# 2_PMIC_2.net
KiCad netlist of a schematic drawn in Altium Designer
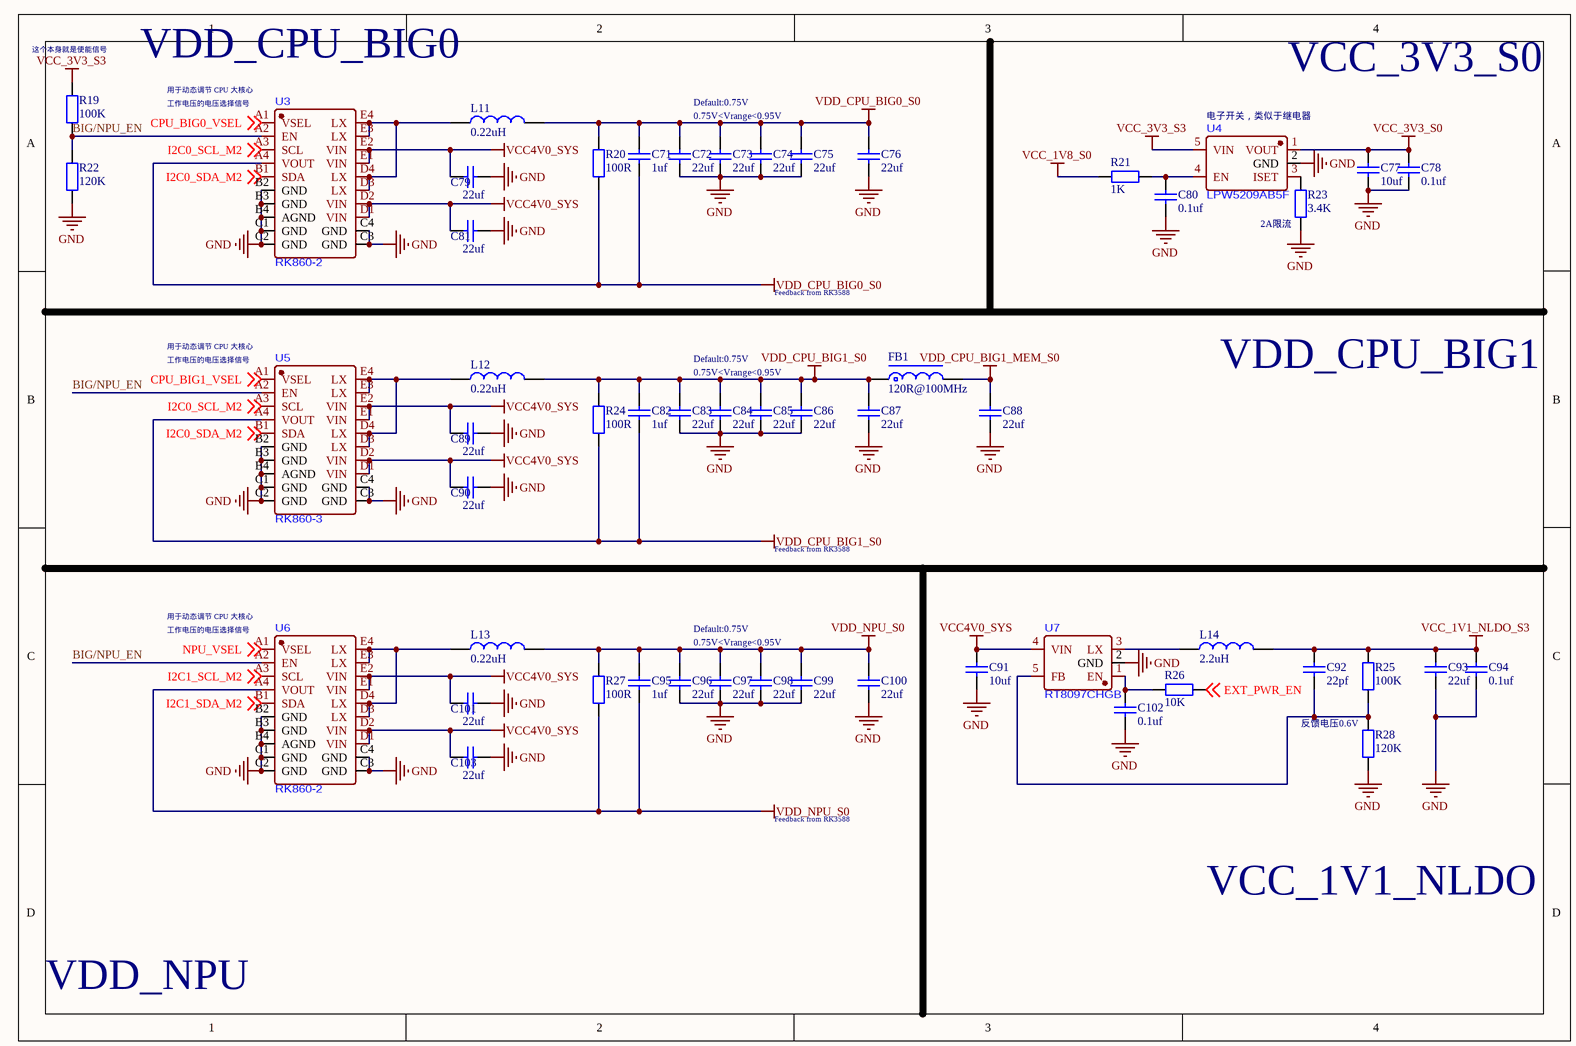
[diagram p0: 2.PMIC_2.SchDoc]

(export (version "E")
  (design (tool "Eeschema 10.0.6"))
  (components
    (comp (ref "C71")
      (value "1uf")
      (footprint "0.PCB1:C0402_L")
      (description "贴片电容/MLCC电容")
      (libsource (lib "RK3588") (part "C"))
    )
    (comp (ref "C72")
      (value "22uf")
      (footprint "0.PCB1:C0603_L")
      (description "贴片电容/MLCC电容")
      (libsource (lib "RK3588") (part "C"))
    )
    (comp (ref "C73")
      (value "22uf")
      (footprint "0.PCB1:C0603_L")
      (description "贴片电容/MLCC电容")
      (libsource (lib "RK3588") (part "C"))
    )
    (comp (ref "C74")
      (value "22uf")
      (footprint "0.PCB1:C0603_L")
      (description "贴片电容/MLCC电容")
      (libsource (lib "RK3588") (part "C"))
    )
    (comp (ref "C75")
      (value "22uf")
      (footprint "0.PCB1:C0603_L")
      (description "贴片电容/MLCC电容")
      (libsource (lib "RK3588") (part "C"))
    )
    (comp (ref "C76")
      (value "22uf")
      (footprint "0.PCB1:C0603_L")
      (description "贴片电容/MLCC电容")
      (libsource (lib "RK3588") (part "C"))
    )
    (comp (ref "C77")
      (value "10uf")
      (footprint "0.PCB1:C0402_L")
      (description "贴片电容/MLCC电容")
      (libsource (lib "RK3588") (part "C"))
    )
    (comp (ref "C78")
      (value "0.1uf")
      (footprint "0.PCB1:C0402_L")
      (description "贴片电容/MLCC电容")
      (libsource (lib "RK3588") (part "C"))
    )
    (comp (ref "C79")
      (value "22uf")
      (footprint "0.PCB1:C0603_L")
      (description "贴片电容/MLCC电容")
      (libsource (lib "RK3588") (part "C"))
    )
    (comp (ref "C80")
      (value "0.1uf")
      (footprint "0.PCB1:C0402_L")
      (description "贴片电容/MLCC电容")
      (libsource (lib "RK3588") (part "C"))
    )
    (comp (ref "C81")
      (value "22uf")
      (footprint "0.PCB1:C0603_L")
      (description "贴片电容/MLCC电容")
      (libsource (lib "RK3588") (part "C"))
    )
    (comp (ref "C82")
      (value "1uf")
      (footprint "0.PCB1:C0402_L")
      (description "贴片电容/MLCC电容")
      (libsource (lib "RK3588") (part "C"))
    )
    (comp (ref "C83")
      (value "22uf")
      (footprint "0.PCB1:C0603_L")
      (description "贴片电容/MLCC电容")
      (libsource (lib "RK3588") (part "C"))
    )
    (comp (ref "C84")
      (value "22uf")
      (footprint "0.PCB1:C0603_L")
      (description "贴片电容/MLCC电容")
      (libsource (lib "RK3588") (part "C"))
    )
    (comp (ref "C85")
      (value "22uf")
      (footprint "0.PCB1:C0603_L")
      (description "贴片电容/MLCC电容")
      (libsource (lib "RK3588") (part "C"))
    )
    (comp (ref "C86")
      (value "22uf")
      (footprint "0.PCB1:C0603_L")
      (description "贴片电容/MLCC电容")
      (libsource (lib "RK3588") (part "C"))
    )
    (comp (ref "C87")
      (value "22uf")
      (footprint "0.PCB1:C0603_L")
      (description "贴片电容/MLCC电容")
      (libsource (lib "RK3588") (part "C"))
    )
    (comp (ref "C88")
      (value "22uf")
      (footprint "0.PCB1:C0603_L")
      (description "贴片电容/MLCC电容")
      (libsource (lib "RK3588") (part "C"))
    )
    (comp (ref "C89")
      (value "22uf")
      (footprint "0.PCB1:C0603_L")
      (description "贴片电容/MLCC电容")
      (libsource (lib "RK3588") (part "C"))
    )
    (comp (ref "C90")
      (value "22uf")
      (footprint "0.PCB1:C0603_L")
      (description "贴片电容/MLCC电容")
      (libsource (lib "RK3588") (part "C"))
    )
    (comp (ref "C91")
      (value "10uf")
      (footprint "0.PCB1:C0402_L")
      (description "贴片电容/MLCC电容")
      (libsource (lib "RK3588") (part "C"))
    )
    (comp (ref "C92")
      (value "22pf")
      (footprint "0.PCB1:C0402_L")
      (description "贴片电容/MLCC电容")
      (libsource (lib "RK3588") (part "C"))
    )
    (comp (ref "C93")
      (value "22uf")
      (footprint "0.PCB1:C0603_L")
      (description "贴片电容/MLCC电容")
      (libsource (lib "RK3588") (part "C"))
    )
    (comp (ref "C94")
      (value "0.1uf")
      (footprint "0.PCB1:C0402_L")
      (description "贴片电容/MLCC电容")
      (libsource (lib "RK3588") (part "C"))
    )
    (comp (ref "C95")
      (value "1uf")
      (footprint "0.PCB1:C0402_L")
      (description "贴片电容/MLCC电容")
      (libsource (lib "RK3588") (part "C"))
    )
    (comp (ref "C96")
      (value "22uf")
      (footprint "0.PCB1:C0603_L")
      (description "贴片电容/MLCC电容")
      (libsource (lib "RK3588") (part "C"))
    )
    (comp (ref "C97")
      (value "22uf")
      (footprint "0.PCB1:C0603_L")
      (description "贴片电容/MLCC电容")
      (libsource (lib "RK3588") (part "C"))
    )
    (comp (ref "C98")
      (value "22uf")
      (footprint "0.PCB1:C0603_L")
      (description "贴片电容/MLCC电容")
      (libsource (lib "RK3588") (part "C"))
    )
    (comp (ref "C99")
      (value "22uf")
      (footprint "0.PCB1:C0603_L")
      (description "贴片电容/MLCC电容")
      (libsource (lib "RK3588") (part "C"))
    )
    (comp (ref "C100")
      (value "22uf")
      (footprint "0.PCB1:C0603_L")
      (description "贴片电容/MLCC电容")
      (libsource (lib "RK3588") (part "C"))
    )
    (comp (ref "C101")
      (value "22uf")
      (footprint "0.PCB1:C0603_L")
      (description "贴片电容/MLCC电容")
      (libsource (lib "RK3588") (part "C"))
    )
    (comp (ref "C102")
      (value "0.1uf")
      (footprint "0.PCB1:C0402_L")
      (description "贴片电容/MLCC电容")
      (libsource (lib "RK3588") (part "C"))
    )
    (comp (ref "C103")
      (value "22uf")
      (footprint "0.PCB1:C0603_L")
      (description "贴片电容/MLCC电容")
      (libsource (lib "RK3588") (part "C"))
    )
    (comp (ref "FB1")
      (value "120R@100MHz")
      (footprint "0.PCB1:FB0402")
      (description "贴片磁珠")
      (libsource (lib "RK3588") (part "FB"))
    )
    (comp (ref "L11")
      (value "0.22uH")
      (footprint "0.PCB1:L0805")
      (description "贴片小功率电感")
      (libsource (lib "RK3588") (part "L"))
    )
    (comp (ref "L12")
      (value "0.22uH")
      (footprint "0.PCB1:L0805")
      (description "贴片小功率电感")
      (libsource (lib "RK3588") (part "L"))
    )
    (comp (ref "L13")
      (value "0.22uH")
      (footprint "0.PCB1:L0805")
      (description "贴片小功率电感")
      (libsource (lib "RK3588") (part "L"))
    )
    (comp (ref "L14")
      (value "2.2uH")
      (footprint "0.PCB1:L0805")
      (description "贴片小功率电感")
      (libsource (lib "RK3588") (part "L"))
    )
    (comp (ref "R19")
      (value "100K")
      (footprint "0.PCB1:R0402_L")
      (description "贴片电阻")
      (libsource (lib "RK3588") (part "R"))
    )
    (comp (ref "R20")
      (value "100R")
      (footprint "0.PCB1:R0402_L")
      (description "贴片电阻")
      (libsource (lib "RK3588") (part "R"))
    )
    (comp (ref "R21")
      (value "1K")
      (footprint "0.PCB1:R0402_L")
      (description "贴片电阻")
      (libsource (lib "RK3588") (part "R"))
    )
    (comp (ref "R22")
      (value "120K")
      (footprint "0.PCB1:R0402_L")
      (description "贴片电阻")
      (libsource (lib "RK3588") (part "R"))
    )
    (comp (ref "R23")
      (value "3.4K")
      (footprint "0.PCB1:R0402_L")
      (description "贴片电阻")
      (libsource (lib "RK3588") (part "R"))
    )
    (comp (ref "R24")
      (value "100R")
      (footprint "0.PCB1:R0402_L")
      (description "贴片电阻")
      (libsource (lib "RK3588") (part "R"))
    )
    (comp (ref "R25")
      (value "100K")
      (footprint "0.PCB1:R0402_L")
      (description "贴片电阻")
      (libsource (lib "RK3588") (part "R"))
    )
    (comp (ref "R26")
      (value "10K")
      (footprint "0.PCB1:R0402_L")
      (description "贴片电阻")
      (libsource (lib "RK3588") (part "R"))
    )
    (comp (ref "R27")
      (value "100R")
      (footprint "0.PCB1:R0402_L")
      (description "贴片电阻")
      (libsource (lib "RK3588") (part "R"))
    )
    (comp (ref "R28")
      (value "120K")
      (footprint "0.PCB1:R0402_L")
      (description "贴片电阻")
      (libsource (lib "RK3588") (part "R"))
    )
    (comp (ref "U3")
      (value "RK860-2")
      (footprint "0.PCB1:WLCSP-20_L2.0-W1.6-R5-C4-P0.40-TL")
      (libsource (lib "RK3588") (part "RK860-2"))
    )
    (comp (ref "U4")
      (value "LPW5209AB5F")
      (footprint "0.PCB1:SOT-23-5_L3.0-W1.7-P0.95-LS2.8-BL")
      (libsource (lib "RK3588") (part "LPW5209AB5F"))
    )
    (comp (ref "U5")
      (value "RK860-3")
      (footprint "0.PCB1:WLCSP-20_L2.0-W1.6-R5-C4-P0.40-TL")
      (libsource (lib "RK3588") (part "RK860-3"))
    )
    (comp (ref "U6")
      (value "RK860-2")
      (footprint "0.PCB1:WLCSP-20_L2.0-W1.6-R5-C4-P0.40-TL")
      (libsource (lib "RK3588") (part "RK860-2"))
    )
    (comp (ref "U7")
      (value "RT8097CHGB")
      (footprint "0.PCB1:SOT-23-5_L3.0-W1.7-P0.95-LS2.8-BR")
      (libsource (lib "RK3588") (part "RT8097CHGB"))
    )
  )
  (nets
    (net (code "1") (name "/BIG{slash}NPU_EN") (class "Default")
      (node (ref "R19") (pin "1") (pinfunction "1_1") (pintype "passive"))
      (node (ref "R22") (pin "2") (pinfunction "2_2") (pintype "passive"))
      (node (ref "U3") (pin "A2") (pinfunction "EN_A2") (pintype "passive"))
      (node (ref "U5") (pin "A2") (pinfunction "EN_A2") (pintype "passive"))
      (node (ref "U6") (pin "A2") (pinfunction "EN_A2") (pintype "passive"))
    )
    (net (code "2") (name "CPU_BIG0_VSEL") (class "Default")
      (node (ref "U3") (pin "A1") (pinfunction "VSEL_A1") (pintype "passive"))
    )
    (net (code "3") (name "CPU_BIG1_VSEL") (class "Default")
      (node (ref "U5") (pin "A1") (pinfunction "VSEL_A1") (pintype "passive"))
    )
    (net (code "4") (name "EXT_PWR_EN") (class "Default")
      (node (ref "R26") (pin "2") (pinfunction "2_2") (pintype "passive"))
    )
    (net (code "5") (name "GND") (class "Default")
      (node (ref "C100") (pin "1") (pinfunction "1_1") (pintype "passive"))
      (node (ref "C101") (pin "1") (pinfunction "1_1") (pintype "passive"))
      (node (ref "C102") (pin "1") (pinfunction "1_1") (pintype "passive"))
      (node (ref "C103") (pin "1") (pinfunction "1_1") (pintype "passive"))
      (node (ref "C72") (pin "1") (pinfunction "1_1") (pintype "passive"))
      (node (ref "C73") (pin "1") (pinfunction "1_1") (pintype "passive"))
      (node (ref "C74") (pin "1") (pinfunction "1_1") (pintype "passive"))
      (node (ref "C75") (pin "1") (pinfunction "1_1") (pintype "passive"))
      (node (ref "C76") (pin "1") (pinfunction "1_1") (pintype "passive"))
      (node (ref "C77") (pin "1") (pinfunction "1_1") (pintype "passive"))
      (node (ref "C78") (pin "1") (pinfunction "1_1") (pintype "passive"))
      (node (ref "C79") (pin "1") (pinfunction "1_1") (pintype "passive"))
      (node (ref "C80") (pin "1") (pinfunction "1_1") (pintype "passive"))
      (node (ref "C81") (pin "1") (pinfunction "1_1") (pintype "passive"))
      (node (ref "C83") (pin "1") (pinfunction "1_1") (pintype "passive"))
      (node (ref "C84") (pin "1") (pinfunction "1_1") (pintype "passive"))
      (node (ref "C85") (pin "1") (pinfunction "1_1") (pintype "passive"))
      (node (ref "C86") (pin "1") (pinfunction "1_1") (pintype "passive"))
      (node (ref "C87") (pin "1") (pinfunction "1_1") (pintype "passive"))
      (node (ref "C88") (pin "1") (pinfunction "1_1") (pintype "passive"))
      (node (ref "C89") (pin "1") (pinfunction "1_1") (pintype "passive"))
      (node (ref "C90") (pin "1") (pinfunction "1_1") (pintype "passive"))
      (node (ref "C91") (pin "2") (pinfunction "2_2") (pintype "passive"))
      (node (ref "C93") (pin "1") (pinfunction "1_1") (pintype "passive"))
      (node (ref "C94") (pin "1") (pinfunction "1_1") (pintype "passive"))
      (node (ref "C96") (pin "1") (pinfunction "1_1") (pintype "passive"))
      (node (ref "C97") (pin "1") (pinfunction "1_1") (pintype "passive"))
      (node (ref "C98") (pin "1") (pinfunction "1_1") (pintype "passive"))
      (node (ref "C99") (pin "1") (pinfunction "1_1") (pintype "passive"))
      (node (ref "R22") (pin "1") (pinfunction "1_1") (pintype "passive"))
      (node (ref "R23") (pin "1") (pinfunction "1_1") (pintype "passive"))
      (node (ref "R28") (pin "1") (pinfunction "1_1") (pintype "passive"))
      (node (ref "U3") (pin "B2") (pinfunction "GND_B2") (pintype "passive"))
      (node (ref "U3") (pin "B3") (pinfunction "GND_B3") (pintype "passive"))
      (node (ref "U3") (pin "B4") (pinfunction "AGND_B4") (pintype "passive"))
      (node (ref "U3") (pin "C1") (pinfunction "GND_C1") (pintype "passive"))
      (node (ref "U3") (pin "C2") (pinfunction "GND_C2") (pintype "passive"))
      (node (ref "U3") (pin "C3") (pinfunction "GND_C3") (pintype "passive"))
      (node (ref "U3") (pin "C4") (pinfunction "GND_C4") (pintype "passive"))
      (node (ref "U4") (pin "2") (pinfunction "GND_2") (pintype "passive"))
      (node (ref "U5") (pin "B2") (pinfunction "GND_B2") (pintype "passive"))
      (node (ref "U5") (pin "B3") (pinfunction "GND_B3") (pintype "passive"))
      (node (ref "U5") (pin "B4") (pinfunction "AGND_B4") (pintype "passive"))
      (node (ref "U5") (pin "C1") (pinfunction "GND_C1") (pintype "passive"))
      (node (ref "U5") (pin "C2") (pinfunction "GND_C2") (pintype "passive"))
      (node (ref "U5") (pin "C3") (pinfunction "GND_C3") (pintype "passive"))
      (node (ref "U5") (pin "C4") (pinfunction "GND_C4") (pintype "passive"))
      (node (ref "U6") (pin "B2") (pinfunction "GND_B2") (pintype "passive"))
      (node (ref "U6") (pin "B3") (pinfunction "GND_B3") (pintype "passive"))
      (node (ref "U6") (pin "B4") (pinfunction "AGND_B4") (pintype "passive"))
      (node (ref "U6") (pin "C1") (pinfunction "GND_C1") (pintype "passive"))
      (node (ref "U6") (pin "C2") (pinfunction "GND_C2") (pintype "passive"))
      (node (ref "U6") (pin "C3") (pinfunction "GND_C3") (pintype "passive"))
      (node (ref "U6") (pin "C4") (pinfunction "GND_C4") (pintype "passive"))
      (node (ref "U7") (pin "2") (pinfunction "GND_2") (pintype "passive"))
    )
    (net (code "6") (name "I2C0_SCL_M2") (class "Default")
      (node (ref "U3") (pin "A3") (pinfunction "SCL_A3") (pintype "passive"))
      (node (ref "U5") (pin "A3") (pinfunction "SCL_A3") (pintype "passive"))
    )
    (net (code "7") (name "I2C0_SDA_M2") (class "Default")
      (node (ref "U3") (pin "B1") (pinfunction "SDA_B1") (pintype "passive"))
      (node (ref "U5") (pin "B1") (pinfunction "SDA_B1") (pintype "passive"))
    )
    (net (code "8") (name "I2C1_SCL_M2") (class "Default")
      (node (ref "U6") (pin "A3") (pinfunction "SCL_A3") (pintype "passive"))
    )
    (net (code "9") (name "I2C1_SDA_M2") (class "Default")
      (node (ref "U6") (pin "B1") (pinfunction "SDA_B1") (pintype "passive"))
    )
    (net (code "10") (name "NPU_VSEL") (class "Default")
      (node (ref "U6") (pin "A1") (pinfunction "VSEL_A1") (pintype "passive"))
    )
    (net (code "11") (name "Net-(L11-Pad1)") (class "Default")
      (node (ref "L11") (pin "1") (pinfunction "1_1") (pintype "passive"))
      (node (ref "U3") (pin "D3") (pinfunction "LX_D3") (pintype "passive"))
      (node (ref "U3") (pin "D4") (pinfunction "LX_D4") (pintype "passive"))
      (node (ref "U3") (pin "E3") (pinfunction "LX_E3") (pintype "passive"))
      (node (ref "U3") (pin "E4") (pinfunction "LX_E4") (pintype "passive"))
    )
    (net (code "12") (name "Net-(L12-Pad1)") (class "Default")
      (node (ref "L12") (pin "1") (pinfunction "1_1") (pintype "passive"))
      (node (ref "U5") (pin "D3") (pinfunction "LX_D3") (pintype "passive"))
      (node (ref "U5") (pin "D4") (pinfunction "LX_D4") (pintype "passive"))
      (node (ref "U5") (pin "E3") (pinfunction "LX_E3") (pintype "passive"))
      (node (ref "U5") (pin "E4") (pinfunction "LX_E4") (pintype "passive"))
    )
    (net (code "13") (name "Net-(L13-Pad1)") (class "Default")
      (node (ref "L13") (pin "1") (pinfunction "1_1") (pintype "passive"))
      (node (ref "U6") (pin "D3") (pinfunction "LX_D3") (pintype "passive"))
      (node (ref "U6") (pin "D4") (pinfunction "LX_D4") (pintype "passive"))
      (node (ref "U6") (pin "E3") (pinfunction "LX_E3") (pintype "passive"))
      (node (ref "U6") (pin "E4") (pinfunction "LX_E4") (pintype "passive"))
    )
    (net (code "14") (name "Net-(U4-EN)") (class "Default")
      (node (ref "C80") (pin "2") (pinfunction "2_2") (pintype "passive"))
      (node (ref "R21") (pin "2") (pinfunction "2_2") (pintype "passive"))
      (node (ref "U4") (pin "4") (pinfunction "EN_4") (pintype "passive"))
    )
    (net (code "15") (name "Net-(U4-ISET)") (class "Default")
      (node (ref "R23") (pin "2") (pinfunction "2_2") (pintype "passive"))
      (node (ref "U4") (pin "3") (pinfunction "ISET_3") (pintype "passive"))
    )
    (net (code "16") (name "Net-(U7-EN)") (class "Default")
      (node (ref "C102") (pin "2") (pinfunction "2_2") (pintype "passive"))
      (node (ref "R26") (pin "1") (pinfunction "1_1") (pintype "passive"))
      (node (ref "U7") (pin "1") (pinfunction "EN_1") (pintype "passive"))
    )
    (net (code "17") (name "Net-(U7-FB)") (class "Default")
      (node (ref "C92") (pin "1") (pinfunction "1_1") (pintype "passive"))
      (node (ref "R25") (pin "1") (pinfunction "1_1") (pintype "passive"))
      (node (ref "R28") (pin "2") (pinfunction "2_2") (pintype "passive"))
      (node (ref "U7") (pin "5") (pinfunction "FB_5") (pintype "passive"))
    )
    (net (code "18") (name "Net-(U7-LX)") (class "Default")
      (node (ref "L14") (pin "1") (pinfunction "1_1") (pintype "passive"))
      (node (ref "U7") (pin "3") (pinfunction "LX_3") (pintype "passive"))
    )
    (net (code "19") (name "VCC4V0_SYS") (class "Default")
      (node (ref "C101") (pin "2") (pinfunction "2_2") (pintype "passive"))
      (node (ref "C103") (pin "2") (pinfunction "2_2") (pintype "passive"))
      (node (ref "C79") (pin "2") (pinfunction "2_2") (pintype "passive"))
      (node (ref "C81") (pin "2") (pinfunction "2_2") (pintype "passive"))
      (node (ref "C89") (pin "2") (pinfunction "2_2") (pintype "passive"))
      (node (ref "C90") (pin "2") (pinfunction "2_2") (pintype "passive"))
      (node (ref "C91") (pin "1") (pinfunction "1_1") (pintype "passive"))
      (node (ref "U3") (pin "D1") (pinfunction "VIN_D1") (pintype "passive"))
      (node (ref "U3") (pin "D2") (pinfunction "VIN_D2") (pintype "passive"))
      (node (ref "U3") (pin "E1") (pinfunction "VIN_E1") (pintype "passive"))
      (node (ref "U3") (pin "E2") (pinfunction "VIN_E2") (pintype "passive"))
      (node (ref "U5") (pin "D1") (pinfunction "VIN_D1") (pintype "passive"))
      (node (ref "U5") (pin "D2") (pinfunction "VIN_D2") (pintype "passive"))
      (node (ref "U5") (pin "E1") (pinfunction "VIN_E1") (pintype "passive"))
      (node (ref "U5") (pin "E2") (pinfunction "VIN_E2") (pintype "passive"))
      (node (ref "U6") (pin "D1") (pinfunction "VIN_D1") (pintype "passive"))
      (node (ref "U6") (pin "D2") (pinfunction "VIN_D2") (pintype "passive"))
      (node (ref "U6") (pin "E1") (pinfunction "VIN_E1") (pintype "passive"))
      (node (ref "U6") (pin "E2") (pinfunction "VIN_E2") (pintype "passive"))
      (node (ref "U7") (pin "4") (pinfunction "VIN_4") (pintype "passive"))
    )
    (net (code "20") (name "VCC_1V1_NLDO_S3") (class "Default")
      (node (ref "C92") (pin "2") (pinfunction "2_2") (pintype "passive"))
      (node (ref "C93") (pin "2") (pinfunction "2_2") (pintype "passive"))
      (node (ref "C94") (pin "2") (pinfunction "2_2") (pintype "passive"))
      (node (ref "L14") (pin "2") (pinfunction "2_2") (pintype "passive"))
      (node (ref "R25") (pin "2") (pinfunction "2_2") (pintype "passive"))
    )
    (net (code "21") (name "VCC_1V8_S0") (class "Default")
      (node (ref "R21") (pin "1") (pinfunction "1_1") (pintype "passive"))
    )
    (net (code "22") (name "VCC_3V3_S0") (class "Default")
      (node (ref "C77") (pin "2") (pinfunction "2_2") (pintype "passive"))
      (node (ref "C78") (pin "2") (pinfunction "2_2") (pintype "passive"))
      (node (ref "U4") (pin "1") (pinfunction "VOUT_1") (pintype "passive"))
    )
    (net (code "23") (name "VCC_3V3_S3") (class "Default")
      (node (ref "R19") (pin "2") (pinfunction "2_2") (pintype "passive"))
      (node (ref "U4") (pin "5") (pinfunction "VIN_5") (pintype "passive"))
    )
    (net (code "24") (name "VDD_CPU_BIG0_S0") (class "Default")
      (node (ref "C71") (pin "1") (pinfunction "1_1") (pintype "passive"))
      (node (ref "C71") (pin "2") (pinfunction "2_2") (pintype "passive"))
      (node (ref "C72") (pin "2") (pinfunction "2_2") (pintype "passive"))
      (node (ref "C73") (pin "2") (pinfunction "2_2") (pintype "passive"))
      (node (ref "C74") (pin "2") (pinfunction "2_2") (pintype "passive"))
      (node (ref "C75") (pin "2") (pinfunction "2_2") (pintype "passive"))
      (node (ref "C76") (pin "2") (pinfunction "2_2") (pintype "passive"))
      (node (ref "L11") (pin "2") (pinfunction "2_2") (pintype "passive"))
      (node (ref "R20") (pin "1") (pinfunction "1_1") (pintype "passive"))
      (node (ref "R20") (pin "2") (pinfunction "2_2") (pintype "passive"))
      (node (ref "U3") (pin "A4") (pinfunction "VOUT_A4") (pintype "passive"))
    )
    (net (code "25") (name "VDD_CPU_BIG1_MEM_S0") (class "Default")
      (node (ref "C88") (pin "2") (pinfunction "2_2") (pintype "passive"))
      (node (ref "FB1") (pin "2") (pinfunction "2_2") (pintype "passive"))
    )
    (net (code "26") (name "VDD_CPU_BIG1_S0") (class "Default")
      (node (ref "C82") (pin "1") (pinfunction "1_1") (pintype "passive"))
      (node (ref "C82") (pin "2") (pinfunction "2_2") (pintype "passive"))
      (node (ref "C83") (pin "2") (pinfunction "2_2") (pintype "passive"))
      (node (ref "C84") (pin "2") (pinfunction "2_2") (pintype "passive"))
      (node (ref "C85") (pin "2") (pinfunction "2_2") (pintype "passive"))
      (node (ref "C86") (pin "2") (pinfunction "2_2") (pintype "passive"))
      (node (ref "C87") (pin "2") (pinfunction "2_2") (pintype "passive"))
      (node (ref "FB1") (pin "1") (pinfunction "1_1") (pintype "passive"))
      (node (ref "L12") (pin "2") (pinfunction "2_2") (pintype "passive"))
      (node (ref "R24") (pin "1") (pinfunction "1_1") (pintype "passive"))
      (node (ref "R24") (pin "2") (pinfunction "2_2") (pintype "passive"))
      (node (ref "U5") (pin "A4") (pinfunction "VOUT_A4") (pintype "passive"))
    )
    (net (code "27") (name "VDD_NPU_S0") (class "Default")
      (node (ref "C100") (pin "2") (pinfunction "2_2") (pintype "passive"))
      (node (ref "C95") (pin "1") (pinfunction "1_1") (pintype "passive"))
      (node (ref "C95") (pin "2") (pinfunction "2_2") (pintype "passive"))
      (node (ref "C96") (pin "2") (pinfunction "2_2") (pintype "passive"))
      (node (ref "C97") (pin "2") (pinfunction "2_2") (pintype "passive"))
      (node (ref "C98") (pin "2") (pinfunction "2_2") (pintype "passive"))
      (node (ref "C99") (pin "2") (pinfunction "2_2") (pintype "passive"))
      (node (ref "L13") (pin "2") (pinfunction "2_2") (pintype "passive"))
      (node (ref "R27") (pin "1") (pinfunction "1_1") (pintype "passive"))
      (node (ref "R27") (pin "2") (pinfunction "2_2") (pintype "passive"))
      (node (ref "U6") (pin "A4") (pinfunction "VOUT_A4") (pintype "passive"))
    )
  )
)
